# Netzgereat.net
KiCad netlist of a schematic drawn in EAGLE
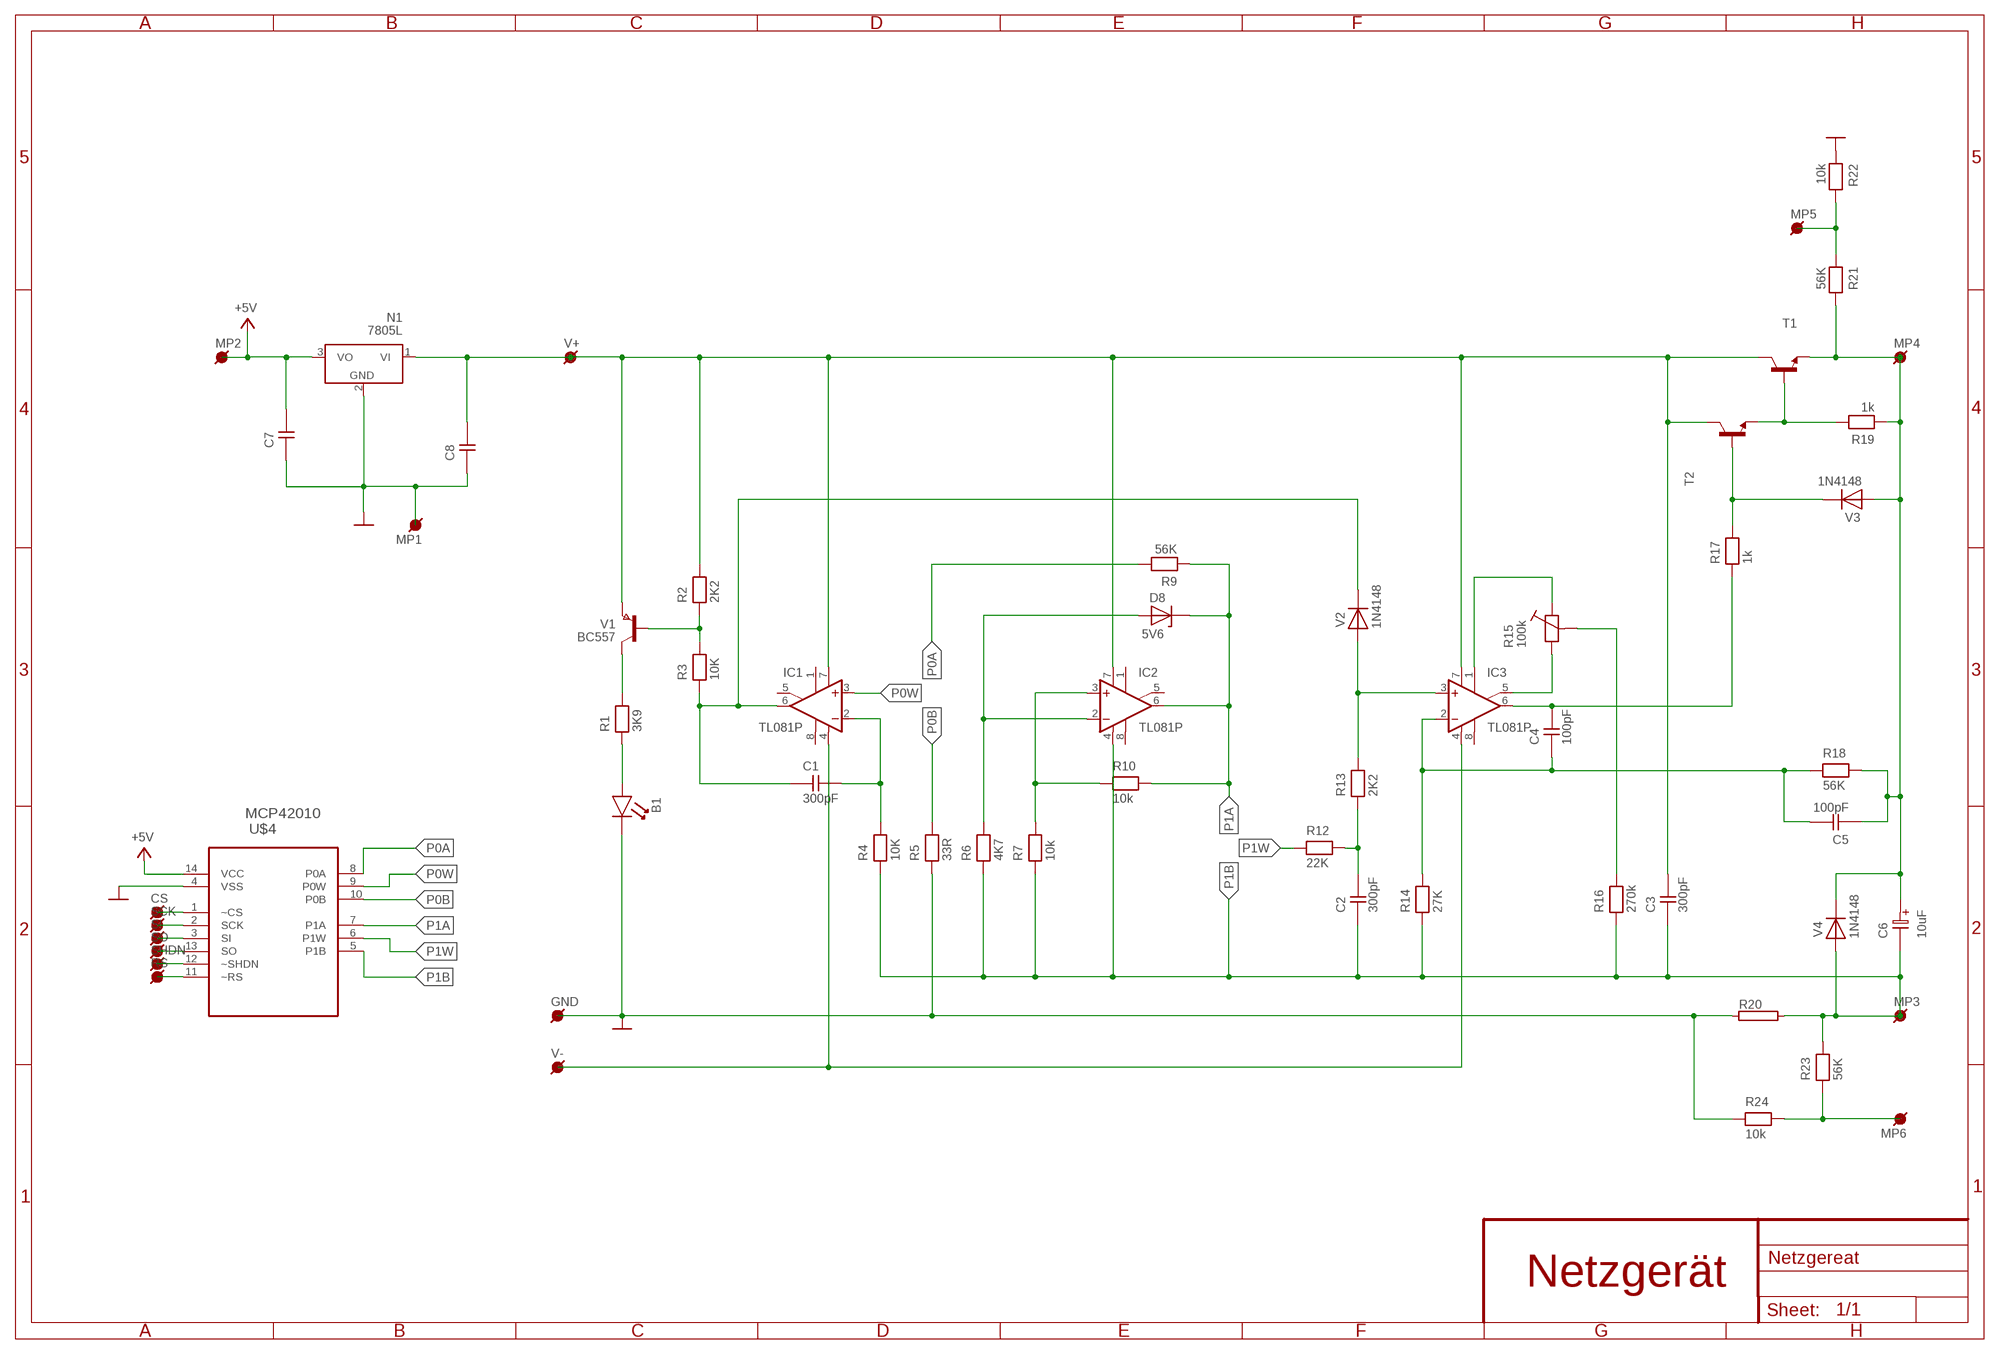
[diagram p0: schematic, sheet 1]

(export (version "E")
  (design (tool "Eeschema 10.0.6"))
  (components
    (comp (ref "B1")
      (value "LED")
      (footprint "eagle-import:LED")
      (libsource (lib "eagle-import") (part "LED"))
    )
    (comp (ref "C1")
      (value "300pF")
      (footprint "eagle-import:C-5")
      (libsource (lib "eagle-import") (part "C-5"))
    )
    (comp (ref "C2")
      (value "300pF")
      (footprint "eagle-import:C-5")
      (libsource (lib "eagle-import") (part "C-5"))
    )
    (comp (ref "C3")
      (value "300pF")
      (footprint "eagle-import:C-5")
      (libsource (lib "eagle-import") (part "C-5"))
    )
    (comp (ref "C4")
      (value "100pF")
      (footprint "eagle-import:C-5")
      (libsource (lib "eagle-import") (part "C-5"))
    )
    (comp (ref "C5")
      (value "100pF")
      (footprint "eagle-import:C-5")
      (libsource (lib "eagle-import") (part "C-5"))
    )
    (comp (ref "C6")
      (value "10uF")
      (footprint "eagle-import:ES-5")
      (libsource (lib "eagle-import") (part "ELC-5"))
    )
    (comp (ref "C7")
      (value "C-5")
      (footprint "eagle-import:C-5")
      (libsource (lib "eagle-import") (part "C-5"))
    )
    (comp (ref "C8")
      (value "C-5")
      (footprint "eagle-import:C-5")
      (libsource (lib "eagle-import") (part "C-5"))
    )
    (comp (ref "CS") (value "MP") (footprint "eagle-import:MP") (libsource (lib "eagle-import") (part "MP")))
    (comp (ref "D8")
      (value "5V6")
      (footprint "eagle-import:D-7,5")
      (libsource (lib "eagle-import") (part "ZD-7.5"))
    )
    (comp (ref "GND") (value "MP") (footprint "eagle-import:MP") (libsource (lib "eagle-import") (part "MP")))
    (comp (ref "IC1")
      (value "TL081P")
      (footprint "eagle-import:DIL08")
      (libsource (lib "eagle-import") (part "TL081P"))
    )
    (comp (ref "IC2")
      (value "TL081P")
      (footprint "eagle-import:DIL08")
      (libsource (lib "eagle-import") (part "TL081P"))
    )
    (comp (ref "IC3")
      (value "TL081P")
      (footprint "eagle-import:DIL08")
      (libsource (lib "eagle-import") (part "TL081P"))
    )
    (comp (ref "MP1") (value "MP") (footprint "eagle-import:MP") (libsource (lib "eagle-import") (part "MP")))
    (comp (ref "MP2") (value "MP") (footprint "eagle-import:MP") (libsource (lib "eagle-import") (part "MP")))
    (comp (ref "MP3") (value "MP") (footprint "eagle-import:MP") (libsource (lib "eagle-import") (part "MP")))
    (comp (ref "MP4") (value "MP") (footprint "eagle-import:MP") (libsource (lib "eagle-import") (part "MP")))
    (comp (ref "MP5") (value "MP") (footprint "eagle-import:MP") (libsource (lib "eagle-import") (part "MP")))
    (comp (ref "MP6") (value "MP") (footprint "eagle-import:MP") (libsource (lib "eagle-import") (part "MP")))
    (comp (ref "N1")
      (value "7805L")
      (footprint "eagle-import:T0-92C")
      (libsource (lib "eagle-import") (part "7805L"))
    )
    (comp (ref "R1")
      (value "3K9")
      (footprint "eagle-import:R-10")
      (libsource (lib "eagle-import") (part "R-10"))
    )
    (comp (ref "R2")
      (value "2K2")
      (footprint "eagle-import:R-10")
      (libsource (lib "eagle-import") (part "R-10"))
    )
    (comp (ref "R3")
      (value "10K")
      (footprint "eagle-import:R-10")
      (libsource (lib "eagle-import") (part "R-10"))
    )
    (comp (ref "R4")
      (value "10K")
      (footprint "eagle-import:R-10")
      (libsource (lib "eagle-import") (part "R-10"))
    )
    (comp (ref "R5")
      (value "33R")
      (footprint "eagle-import:R-10")
      (libsource (lib "eagle-import") (part "R-10"))
    )
    (comp (ref "R6")
      (value "4K7")
      (footprint "eagle-import:R-10")
      (libsource (lib "eagle-import") (part "R-10"))
    )
    (comp (ref "R7")
      (value "10k")
      (footprint "eagle-import:R-10")
      (libsource (lib "eagle-import") (part "R-10"))
    )
    (comp (ref "R9")
      (value "56K")
      (footprint "eagle-import:R-10")
      (libsource (lib "eagle-import") (part "R-10"))
    )
    (comp (ref "R10")
      (value "10k")
      (footprint "eagle-import:R-10")
      (libsource (lib "eagle-import") (part "R-10"))
    )
    (comp (ref "R12")
      (value "22K")
      (footprint "eagle-import:R-10")
      (libsource (lib "eagle-import") (part "R-10"))
    )
    (comp (ref "R13")
      (value "2K2")
      (footprint "eagle-import:R-10")
      (libsource (lib "eagle-import") (part "R-10"))
    )
    (comp (ref "R14")
      (value "27K")
      (footprint "eagle-import:R-10")
      (libsource (lib "eagle-import") (part "R-10"))
    )
    (comp (ref "R15")
      (value "100k")
      (footprint "eagle-import:PT-SPIN")
      (libsource (lib "eagle-import") (part "R-TRIM-SPINDEL"))
    )
    (comp (ref "R16")
      (value "270k")
      (footprint "eagle-import:R-10")
      (libsource (lib "eagle-import") (part "R-10"))
    )
    (comp (ref "R17")
      (value "1k")
      (footprint "eagle-import:R-10")
      (libsource (lib "eagle-import") (part "R-10"))
    )
    (comp (ref "R18")
      (value "56K")
      (footprint "eagle-import:R-10")
      (libsource (lib "eagle-import") (part "R-10"))
    )
    (comp (ref "R19")
      (value "1k")
      (footprint "eagle-import:R-10")
      (libsource (lib "eagle-import") (part "R-10"))
    )
    (comp (ref "R20")
      (value "RKH208-8")
      (footprint "eagle-import:KH208-8")
      (libsource (lib "eagle-import") (part "RKH208-8"))
    )
    (comp (ref "R21")
      (value "56K")
      (footprint "eagle-import:R-10")
      (libsource (lib "eagle-import") (part "R-10"))
    )
    (comp (ref "R22")
      (value "10k")
      (footprint "eagle-import:R-10")
      (libsource (lib "eagle-import") (part "R-10"))
    )
    (comp (ref "R23")
      (value "56K")
      (footprint "eagle-import:R-10")
      (libsource (lib "eagle-import") (part "R-10"))
    )
    (comp (ref "R24")
      (value "10k")
      (footprint "eagle-import:R-10")
      (libsource (lib "eagle-import") (part "R-10"))
    )
    (comp (ref "RS") (value "MP") (footprint "eagle-import:MP") (libsource (lib "eagle-import") (part "MP")))
    (comp (ref "SCK") (value "MP") (footprint "eagle-import:MP") (libsource (lib "eagle-import") (part "MP")))
    (comp (ref "SHDN")
      (value "MP")
      (footprint "eagle-import:MP")
      (libsource (lib "eagle-import") (part "MP"))
    )
    (comp (ref "SI") (value "MP") (footprint "eagle-import:MP") (libsource (lib "eagle-import") (part "MP")))
    (comp (ref "SO") (value "MP") (footprint "eagle-import:MP") (libsource (lib "eagle-import") (part "MP")))
    (comp (ref "T1")
      (value "-NPN-TOP3V")
      (footprint "eagle-import:TOP3V")
      (libsource (lib "eagle-import") (part "-NPN-TOP3V"))
    )
    (comp (ref "T2")
      (value "-NPN-TO126V")
      (footprint "eagle-import:TO126V")
      (libsource (lib "eagle-import") (part "-NPN-TO126V"))
    )
    (comp (ref "U$4")
      (value "MCP42010")
      (footprint "eagle-import:MCP42010")
      (libsource (lib "eagle-import") (part "MCP42010"))
    )
    (comp (ref "V+") (value "MP") (footprint "eagle-import:MP") (libsource (lib "eagle-import") (part "MP")))
    (comp (ref "V-") (value "MP") (footprint "eagle-import:MP") (libsource (lib "eagle-import") (part "MP")))
    (comp (ref "V1")
      (value "BC557")
      (footprint "eagle-import:TO-92C")
      (libsource (lib "eagle-import") (part "BC557"))
    )
    (comp (ref "V2")
      (value "1N4148")
      (footprint "eagle-import:D-5")
      (libsource (lib "eagle-import") (part "D-5"))
    )
    (comp (ref "V3")
      (value "1N4148")
      (footprint "eagle-import:D-7,5")
      (libsource (lib "eagle-import") (part "D-7.5"))
    )
    (comp (ref "V4")
      (value "1N4148")
      (footprint "eagle-import:D-5")
      (libsource (lib "eagle-import") (part "D-5"))
    )
  )
  (nets
    (net (code "1") (name "+5V") (class "Default")
      (node (ref "C7") (pin "2") (pinfunction "2_2") (pintype "passive"))
      (node (ref "MP2") (pin "P$1") (pinfunction "MP_P$1") (pintype "passive"))
      (node (ref "N1") (pin "3") (pinfunction "VO_3") (pintype "output"))
      (node (ref "U$4") (pin "14") (pinfunction "VCC_14") (pintype "bidirectional"))
    )
    (net (code "2") (name "GND") (class "Default")
      (node (ref "B1") (pin "2") (pinfunction "K_2") (pintype "passive"))
      (node (ref "C7") (pin "1") (pinfunction "1_1") (pintype "passive"))
      (node (ref "C8") (pin "1") (pinfunction "1_1") (pintype "passive"))
      (node (ref "GND") (pin "P$1") (pinfunction "MP_P$1") (pintype "passive"))
      (node (ref "MP1") (pin "P$1") (pinfunction "MP_P$1") (pintype "passive"))
      (node (ref "N1") (pin "2") (pinfunction "GND_2") (pintype "input"))
      (node (ref "R20") (pin "1") (pinfunction "1_1") (pintype "passive"))
      (node (ref "R22") (pin "1") (pinfunction "1_1") (pintype "passive"))
      (node (ref "R24") (pin "1") (pinfunction "1_1") (pintype "passive"))
      (node (ref "R5") (pin "1") (pinfunction "1_1") (pintype "passive"))
      (node (ref "U$4") (pin "4") (pinfunction "VSS_4") (pintype "bidirectional"))
    )
    (net (code "3") (name "Net-(B1-A)") (class "Default")
      (node (ref "B1") (pin "1") (pinfunction "A_1") (pintype "passive"))
      (node (ref "R1") (pin "1") (pinfunction "1_1") (pintype "passive"))
    )
    (net (code "4") (name "Net-(C2-Pad2)") (class "Default")
      (node (ref "C2") (pin "2") (pinfunction "2_2") (pintype "passive"))
      (node (ref "R12") (pin "2") (pinfunction "2_2") (pintype "passive"))
      (node (ref "R13") (pin "1") (pinfunction "1_1") (pintype "passive"))
    )
    (net (code "5") (name "Net-(CS-MP)") (class "Default")
      (node (ref "CS") (pin "P$1") (pinfunction "MP_P$1") (pintype "passive"))
      (node (ref "U$4") (pin "1") (pinfunction "~{CS}_1") (pintype "bidirectional"))
    )
    (net (code "6") (name "Net-(D8-A)") (class "Default")
      (node (ref "D8") (pin "1") (pinfunction "A_1") (pintype "passive"))
      (node (ref "IC2") (pin "2") (pinfunction "-IN_2") (pintype "input"))
      (node (ref "R6") (pin "2") (pinfunction "2_2") (pintype "passive"))
    )
    (net (code "7") (name "Net-(IC1--IN)") (class "Default")
      (node (ref "C1") (pin "2") (pinfunction "2_2") (pintype "passive"))
      (node (ref "IC1") (pin "2") (pinfunction "-IN_2") (pintype "input"))
      (node (ref "R4") (pin "2") (pinfunction "2_2") (pintype "passive"))
    )
    (net (code "8") (name "Net-(IC1-OUT)") (class "Default")
      (node (ref "C1") (pin "1") (pinfunction "1_1") (pintype "passive"))
      (node (ref "IC1") (pin "6") (pinfunction "OUT_6") (pintype "output"))
      (node (ref "R3") (pin "1") (pinfunction "1_1") (pintype "passive"))
      (node (ref "V2") (pin "2") (pinfunction "K_2") (pintype "passive"))
    )
    (net (code "9") (name "Net-(IC1-V+)") (class "Default")
      (node (ref "C3") (pin "2") (pinfunction "2_2") (pintype "passive"))
      (node (ref "C8") (pin "2") (pinfunction "2_2") (pintype "passive"))
      (node (ref "IC1") (pin "7") (pinfunction "V+_7") (pintype "power_in"))
      (node (ref "IC2") (pin "7") (pinfunction "V+_7") (pintype "power_in"))
      (node (ref "IC3") (pin "7") (pinfunction "V+_7") (pintype "power_in"))
      (node (ref "N1") (pin "1") (pinfunction "VI_1") (pintype "input"))
      (node (ref "R2") (pin "2") (pinfunction "2_2") (pintype "passive"))
      (node (ref "T1") (pin "C") (pinfunction "C_C") (pintype "passive"))
      (node (ref "T2") (pin "2") (pinfunction "C_2") (pintype "passive"))
      (node (ref "V+") (pin "P$1") (pinfunction "MP_P$1") (pintype "passive"))
      (node (ref "V1") (pin "1") (pinfunction "E_1") (pintype "passive"))
    )
    (net (code "10") (name "Net-(IC1-V-)") (class "Default")
      (node (ref "IC1") (pin "4") (pinfunction "V-_4") (pintype "power_in"))
      (node (ref "IC3") (pin "4") (pinfunction "V-_4") (pintype "power_in"))
      (node (ref "V-") (pin "P$1") (pinfunction "MP_P$1") (pintype "passive"))
    )
    (net (code "11") (name "Net-(IC2-+IN)") (class "Default")
      (node (ref "IC2") (pin "3") (pinfunction "+IN_3") (pintype "input"))
      (node (ref "R10") (pin "1") (pinfunction "1_1") (pintype "passive"))
      (node (ref "R7") (pin "2") (pinfunction "2_2") (pintype "passive"))
    )
    (net (code "12") (name "Net-(IC3-+IN)") (class "Default")
      (node (ref "IC3") (pin "3") (pinfunction "+IN_3") (pintype "input"))
      (node (ref "R13") (pin "2") (pinfunction "2_2") (pintype "passive"))
      (node (ref "V2") (pin "1") (pinfunction "A_1") (pintype "passive"))
    )
    (net (code "13") (name "Net-(IC3--IN)") (class "Default")
      (node (ref "C4") (pin "1") (pinfunction "1_1") (pintype "passive"))
      (node (ref "C5") (pin "2") (pinfunction "2_2") (pintype "passive"))
      (node (ref "IC3") (pin "2") (pinfunction "-IN_2") (pintype "input"))
      (node (ref "R14") (pin "2") (pinfunction "2_2") (pintype "passive"))
      (node (ref "R18") (pin "1") (pinfunction "1_1") (pintype "passive"))
    )
    (net (code "14") (name "Net-(IC3-ON1)") (class "Default")
      (node (ref "IC3") (pin "1") (pinfunction "ON1_1") (pintype "passive"))
      (node (ref "R15") (pin "3") (pinfunction "3_3") (pintype "passive"))
    )
    (net (code "15") (name "Net-(IC3-ON2)") (class "Default")
      (node (ref "IC3") (pin "5") (pinfunction "ON2_5") (pintype "passive"))
      (node (ref "R15") (pin "1") (pinfunction "1_1") (pintype "passive"))
    )
    (net (code "16") (name "Net-(IC3-OUT)") (class "Default")
      (node (ref "C4") (pin "2") (pinfunction "2_2") (pintype "passive"))
      (node (ref "IC3") (pin "6") (pinfunction "OUT_6") (pintype "output"))
      (node (ref "R17") (pin "1") (pinfunction "1_1") (pintype "passive"))
    )
    (net (code "17") (name "Net-(MP4-MP)") (class "Default")
      (node (ref "C5") (pin "1") (pinfunction "1_1") (pintype "passive"))
      (node (ref "C6") (pin "1") (pinfunction "1_1") (pintype "passive"))
      (node (ref "MP4") (pin "P$1") (pinfunction "MP_P$1") (pintype "passive"))
      (node (ref "R18") (pin "2") (pinfunction "2_2") (pintype "passive"))
      (node (ref "R19") (pin "1") (pinfunction "1_1") (pintype "passive"))
      (node (ref "R21") (pin "2") (pinfunction "2_2") (pintype "passive"))
      (node (ref "T1") (pin "E") (pinfunction "E_E") (pintype "passive"))
      (node (ref "V3") (pin "1") (pinfunction "A_1") (pintype "passive"))
      (node (ref "V4") (pin "2") (pinfunction "K_2") (pintype "passive"))
    )
    (net (code "18") (name "Net-(MP5-MP)") (class "Default")
      (node (ref "MP5") (pin "P$1") (pinfunction "MP_P$1") (pintype "passive"))
      (node (ref "R21") (pin "1") (pinfunction "1_1") (pintype "passive"))
      (node (ref "R22") (pin "2") (pinfunction "2_2") (pintype "passive"))
    )
    (net (code "19") (name "Net-(MP6-MP)") (class "Default")
      (node (ref "MP6") (pin "P$1") (pinfunction "MP_P$1") (pintype "passive"))
      (node (ref "R23") (pin "1") (pinfunction "1_1") (pintype "passive"))
      (node (ref "R24") (pin "2") (pinfunction "2_2") (pintype "passive"))
    )
    (net (code "20") (name "Net-(R15-Pad2)") (class "Default")
      (node (ref "R15") (pin "2") (pinfunction "2_2") (pintype "passive"))
      (node (ref "R16") (pin "2") (pinfunction "2_2") (pintype "passive"))
    )
    (net (code "21") (name "Net-(RS-MP)") (class "Default")
      (node (ref "RS") (pin "P$1") (pinfunction "MP_P$1") (pintype "passive"))
      (node (ref "U$4") (pin "11") (pinfunction "~{RS}_11") (pintype "bidirectional"))
    )
    (net (code "22") (name "Net-(SCK-MP)") (class "Default")
      (node (ref "SCK") (pin "P$1") (pinfunction "MP_P$1") (pintype "passive"))
      (node (ref "U$4") (pin "2") (pinfunction "SCK_2") (pintype "bidirectional"))
    )
    (net (code "23") (name "Net-(SHDN-MP)") (class "Default")
      (node (ref "SHDN") (pin "P$1") (pinfunction "MP_P$1") (pintype "passive"))
      (node (ref "U$4") (pin "12") (pinfunction "~{SHDN}_12") (pintype "bidirectional"))
    )
    (net (code "24") (name "Net-(SI-MP)") (class "Default")
      (node (ref "SI") (pin "P$1") (pinfunction "MP_P$1") (pintype "passive"))
      (node (ref "U$4") (pin "3") (pinfunction "SI_3") (pintype "bidirectional"))
    )
    (net (code "25") (name "Net-(SO-MP)") (class "Default")
      (node (ref "SO") (pin "P$1") (pinfunction "MP_P$1") (pintype "passive"))
      (node (ref "U$4") (pin "13") (pinfunction "SO_13") (pintype "bidirectional"))
    )
    (net (code "26") (name "Net-(T2-B)") (class "Default")
      (node (ref "R17") (pin "2") (pinfunction "2_2") (pintype "passive"))
      (node (ref "T2") (pin "3") (pinfunction "B_3") (pintype "passive"))
      (node (ref "V3") (pin "2") (pinfunction "K_2") (pintype "passive"))
    )
    (net (code "27") (name "Net-(T2-E)") (class "Default")
      (node (ref "R19") (pin "2") (pinfunction "2_2") (pintype "passive"))
      (node (ref "T1") (pin "B") (pinfunction "B_B") (pintype "passive"))
      (node (ref "T2") (pin "1") (pinfunction "E_1") (pintype "passive"))
    )
    (net (code "28") (name "Net-(V1-B)") (class "Default")
      (node (ref "R2") (pin "1") (pinfunction "1_1") (pintype "passive"))
      (node (ref "R3") (pin "2") (pinfunction "2_2") (pintype "passive"))
      (node (ref "V1") (pin "2") (pinfunction "B_2") (pintype "passive"))
    )
    (net (code "29") (name "Net-(V1-C)") (class "Default")
      (node (ref "R1") (pin "2") (pinfunction "2_2") (pintype "passive"))
      (node (ref "V1") (pin "3") (pinfunction "C_3") (pintype "passive"))
    )
    (net (code "30") (name "P0A") (class "Default")
      (node (ref "R9") (pin "2") (pinfunction "2_2") (pintype "passive"))
      (node (ref "U$4") (pin "8") (pinfunction "P0A_8") (pintype "passive"))
    )
    (net (code "31") (name "P0B") (class "Default")
      (node (ref "R5") (pin "2") (pinfunction "2_2") (pintype "passive"))
      (node (ref "U$4") (pin "10") (pinfunction "P0B_10") (pintype "passive"))
    )
    (net (code "32") (name "P0W") (class "Default")
      (node (ref "IC1") (pin "3") (pinfunction "+IN_3") (pintype "input"))
      (node (ref "U$4") (pin "9") (pinfunction "P0W_9") (pintype "passive"))
    )
    (net (code "33") (name "P1A") (class "Default")
      (node (ref "D8") (pin "2") (pinfunction "K_2") (pintype "passive"))
      (node (ref "IC2") (pin "6") (pinfunction "OUT_6") (pintype "output"))
      (node (ref "R10") (pin "2") (pinfunction "2_2") (pintype "passive"))
      (node (ref "R9") (pin "1") (pinfunction "1_1") (pintype "passive"))
      (node (ref "U$4") (pin "7") (pinfunction "P1A_7") (pintype "passive"))
    )
    (net (code "34") (name "P1B") (class "Default")
      (node (ref "C2") (pin "1") (pinfunction "1_1") (pintype "passive"))
      (node (ref "C3") (pin "1") (pinfunction "1_1") (pintype "passive"))
      (node (ref "C6") (pin "2") (pinfunction "2_2") (pintype "passive"))
      (node (ref "IC2") (pin "4") (pinfunction "V-_4") (pintype "power_in"))
      (node (ref "MP3") (pin "P$1") (pinfunction "MP_P$1") (pintype "passive"))
      (node (ref "R14") (pin "1") (pinfunction "1_1") (pintype "passive"))
      (node (ref "R16") (pin "1") (pinfunction "1_1") (pintype "passive"))
      (node (ref "R20") (pin "2") (pinfunction "2_2") (pintype "passive"))
      (node (ref "R23") (pin "2") (pinfunction "2_2") (pintype "passive"))
      (node (ref "R4") (pin "1") (pinfunction "1_1") (pintype "passive"))
      (node (ref "R6") (pin "1") (pinfunction "1_1") (pintype "passive"))
      (node (ref "R7") (pin "1") (pinfunction "1_1") (pintype "passive"))
      (node (ref "U$4") (pin "5") (pinfunction "P1B_5") (pintype "passive"))
      (node (ref "V4") (pin "1") (pinfunction "A_1") (pintype "passive"))
    )
    (net (code "35") (name "P1W") (class "Default")
      (node (ref "R12") (pin "1") (pinfunction "1_1") (pintype "passive"))
      (node (ref "U$4") (pin "6") (pinfunction "P1W_6") (pintype "passive"))
    )
    (net (code "36") (name "unconnected-(IC1-ON1-Pad1)") (class "Default")
      (node (ref "IC1") (pin "1") (pinfunction "ON1_1") (pintype "passive"))
    )
    (net (code "37") (name "unconnected-(IC1-ON2-Pad5)") (class "Default")
      (node (ref "IC1") (pin "5") (pinfunction "ON2_5") (pintype "passive"))
    )
    (net (code "38") (name "unconnected-(IC1-OPT-Pad8)") (class "Default")
      (node (ref "IC1") (pin "8") (pinfunction "OPT_8") (pintype "passive"))
    )
    (net (code "39") (name "unconnected-(IC2-ON1-Pad1)") (class "Default")
      (node (ref "IC2") (pin "1") (pinfunction "ON1_1") (pintype "passive"))
    )
    (net (code "40") (name "unconnected-(IC2-ON2-Pad5)") (class "Default")
      (node (ref "IC2") (pin "5") (pinfunction "ON2_5") (pintype "passive"))
    )
    (net (code "41") (name "unconnected-(IC2-OPT-Pad8)") (class "Default")
      (node (ref "IC2") (pin "8") (pinfunction "OPT_8") (pintype "passive"))
    )
    (net (code "42") (name "unconnected-(IC3-OPT-Pad8)") (class "Default")
      (node (ref "IC3") (pin "8") (pinfunction "OPT_8") (pintype "passive"))
    )
  )
)
